# Voltage2CurrentSupply.net
KiCad netlist of a schematic drawn in EAGLE
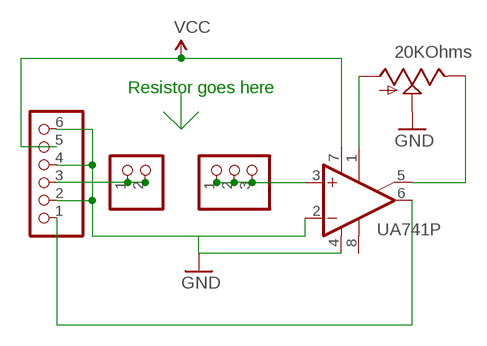
[diagram p0: schematic, sheet 1]

(export (version "E")
  (design (tool "Eeschema 10.0.6"))
  (components
    (comp (ref "IC1")
      (value "UA741P")
      (footprint "eagle-import:DIL08")
      (libsource (lib "eagle-import") (part "741PUA"))
    )
    (comp (ref "JP1")
      (value "PINHD-1X2")
      (footprint "eagle-import:1X02")
      (libsource (lib "eagle-import") (part "PINHD-1X2"))
    )
    (comp (ref "JP2")
      (value "PINHD-1X3")
      (footprint "eagle-import:1X03")
      (libsource (lib "eagle-import") (part "PINHD-1X3"))
    )
    (comp (ref "JP3")
      (value "PINHD-1X6")
      (footprint "eagle-import:1X06")
      (libsource (lib "eagle-import") (part "PINHD-1X6"))
    )
    (comp (ref "RV1")
      (value "20KOhms")
      (footprint "eagle-import:POT_ALPHA_RV16AF-20")
      (libsource (lib "eagle-import") (part "POT-RV16AF-20"))
    )
  )
  (nets
    (net (code "1") (name "GND") (class "Default")
      (node (ref "IC1") (pin "2") (pinfunction "-IN_2") (pintype "input"))
      (node (ref "IC1") (pin "4") (pinfunction "V-_4") (pintype "power_in"))
      (node (ref "JP3") (pin "2") (pinfunction "2_2") (pintype "passive"))
      (node (ref "JP3") (pin "4") (pinfunction "4_4") (pintype "passive"))
      (node (ref "JP3") (pin "6") (pinfunction "6_6") (pintype "passive"))
      (node (ref "RV1") (pin "2") (pinfunction "S_2") (pintype "passive"))
    )
    (net (code "2") (name "Net-(IC1-+IN)") (class "Default")
      (node (ref "IC1") (pin "3") (pinfunction "+IN_3") (pintype "input"))
      (node (ref "JP2") (pin "1") (pinfunction "1_1") (pintype "passive"))
      (node (ref "JP2") (pin "2") (pinfunction "2_2") (pintype "passive"))
      (node (ref "JP2") (pin "3") (pinfunction "3_3") (pintype "passive"))
    )
    (net (code "3") (name "Net-(IC1-ON1)") (class "Default")
      (node (ref "IC1") (pin "1") (pinfunction "ON1_1") (pintype "passive"))
      (node (ref "RV1") (pin "1") (pinfunction "A_1") (pintype "passive"))
    )
    (net (code "4") (name "Net-(IC1-ON2)") (class "Default")
      (node (ref "IC1") (pin "5") (pinfunction "ON2_5") (pintype "passive"))
      (node (ref "RV1") (pin "3") (pinfunction "E_3") (pintype "passive"))
    )
    (net (code "5") (name "Net-(IC1-OUT)") (class "Default")
      (node (ref "IC1") (pin "6") (pinfunction "OUT_6") (pintype "output"))
      (node (ref "JP3") (pin "1") (pinfunction "1_1") (pintype "passive"))
    )
    (net (code "6") (name "Net-(JP1-Pad1)") (class "Default")
      (node (ref "JP1") (pin "1") (pinfunction "1_1") (pintype "passive"))
      (node (ref "JP1") (pin "2") (pinfunction "2_2") (pintype "passive"))
      (node (ref "JP3") (pin "3") (pinfunction "3_3") (pintype "passive"))
    )
    (net (code "7") (name "VCC") (class "Default")
      (node (ref "IC1") (pin "7") (pinfunction "V+_7") (pintype "power_in"))
      (node (ref "JP3") (pin "5") (pinfunction "5_5") (pintype "passive"))
    )
    (net (code "8") (name "unconnected-(IC1-OPT-Pad8)") (class "Default")
      (node (ref "IC1") (pin "8") (pinfunction "OPT_8") (pintype "passive"))
    )
  )
)
